# CW340_SAM3X_PWR.net
KiCad netlist of a schematic drawn in Altium Designer
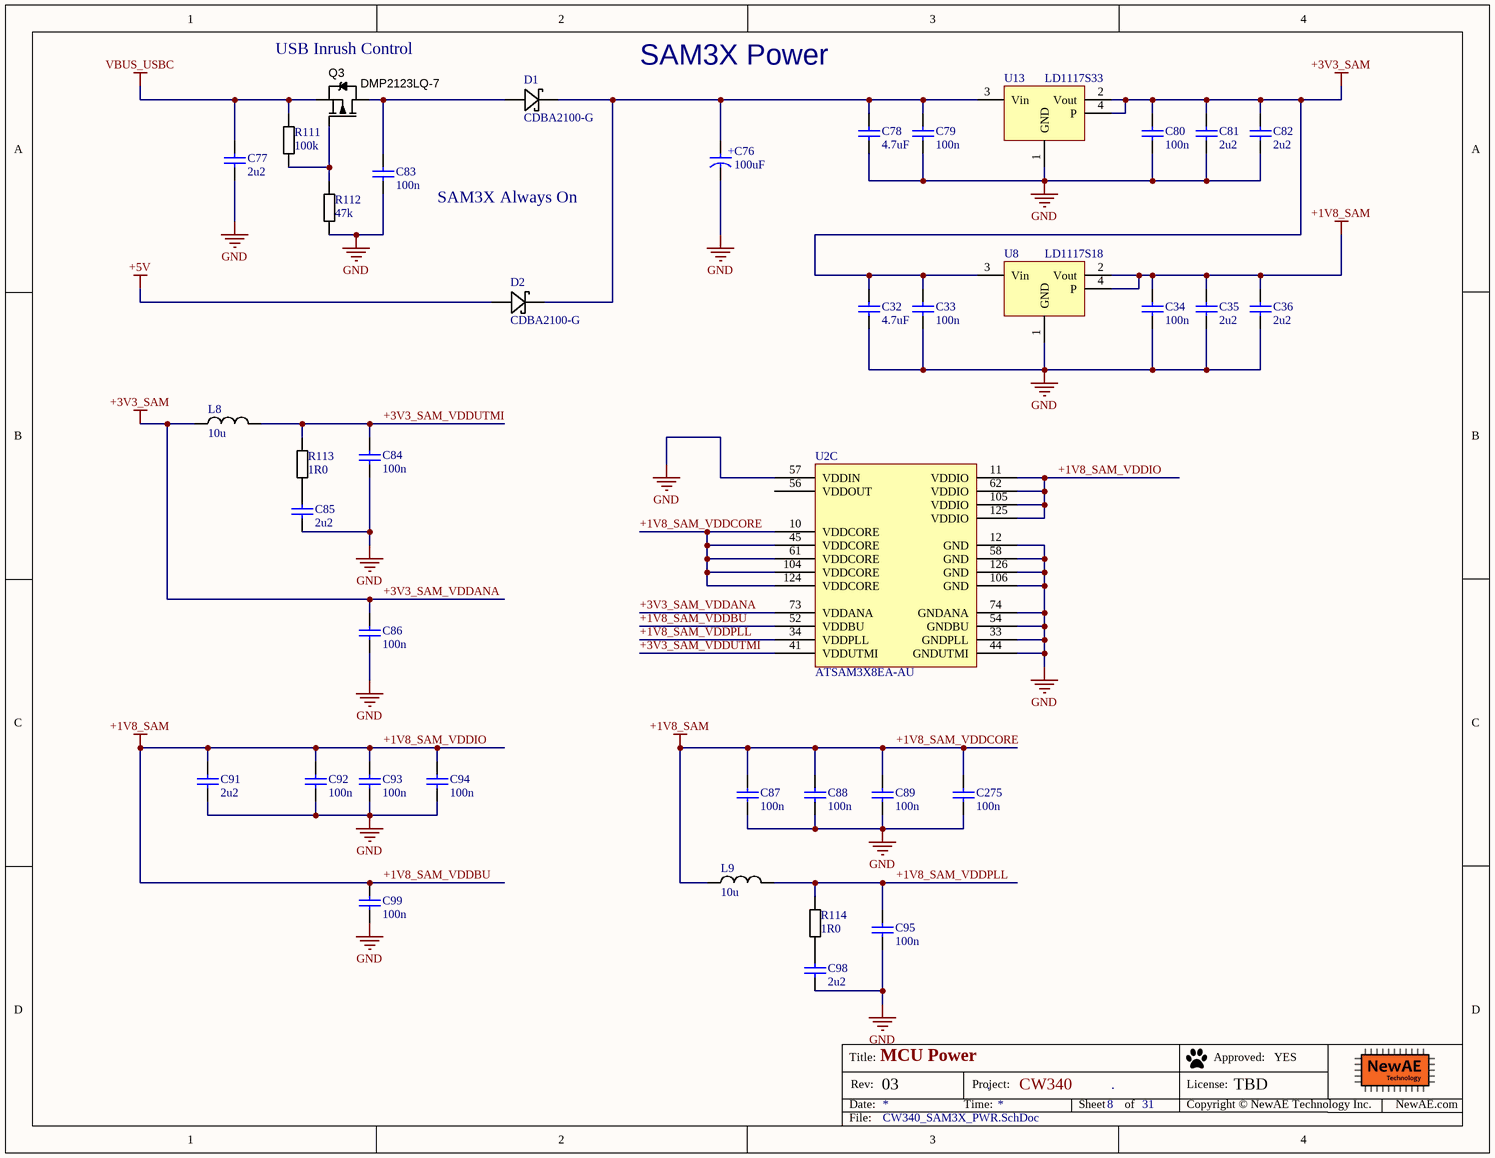
[diagram p0: CW340_SAM3X_PWR.SchDoc]

(export (version "E")
  (design (tool "Eeschema 10.0.6"))
  (components
    (comp (ref "C32")
      (value "4.7uF")
      (footprint "CAPC0805_M")
      (description "4u7, 35V, 0805, Ceramic")
      (fields (field (name "PART NUMBER") "CCHIP-4u7-0805-35V") (field (name "TOLERANCE") "10%"))
      (libsource (lib "NewAE_AltiumLib") (part "CAP"))
    )
    (comp (ref "C33")
      (value "100n")
      (footprint "CAPC0402_M")
      (description "100n, 0402")
      (fields (field (name "PART NUMBER") "CCHIP-100n-0402"))
      (libsource (lib "NewAE_AltiumLib") (part "CAP"))
    )
    (comp (ref "C34")
      (value "100n")
      (footprint "CAPC0402_M")
      (description "100n, 0402")
      (fields (field (name "PART NUMBER") "CCHIP-100n-0402"))
      (libsource (lib "NewAE_AltiumLib") (part "CAP"))
    )
    (comp (ref "C35")
      (value "2u2")
      (footprint "CAPC0603_M")
      (description "2u2, 0603")
      (fields (field (name "PART NUMBER") "CCHIP-2u2-0603"))
      (libsource (lib "NewAE_AltiumLib") (part "CAP"))
    )
    (comp (ref "C36")
      (value "2u2")
      (footprint "CAPC0603_M")
      (description "2u2, 0603")
      (fields (field (name "PART NUMBER") "CCHIP-2u2-0603"))
      (libsource (lib "NewAE_AltiumLib") (part "CAP"))
    )
    (comp (ref "C76")
      (value "100uF")
      (footprint "CAP_AL_D6.3")
      (description "CAP ALUM 100UF 20% 35V RADIAL")
      (fields (field (name "PART NUMBER") "Cap_35v_100uF"))
      (libsource (lib "NewAE_AltiumLib") (part "CAP_POL"))
    )
    (comp (ref "C77")
      (value "2u2")
      (footprint "CAPC0603_M")
      (description "2u2, 0603")
      (fields (field (name "PART NUMBER") "CCHIP-2u2-0603"))
      (libsource (lib "NewAE_AltiumLib") (part "CAP"))
    )
    (comp (ref "C78")
      (value "4.7uF")
      (footprint "CAPC0805_M")
      (description "4u7, 35V, 0805, Ceramic")
      (fields (field (name "PART NUMBER") "CCHIP-4u7-0805-35V") (field (name "TOLERANCE") "10%"))
      (libsource (lib "NewAE_AltiumLib") (part "CAP"))
    )
    (comp (ref "C79")
      (value "100n")
      (footprint "CAPC0402_M")
      (description "100n, 0402")
      (fields (field (name "PART NUMBER") "CCHIP-100n-0402"))
      (libsource (lib "NewAE_AltiumLib") (part "CAP"))
    )
    (comp (ref "C80")
      (value "100n")
      (footprint "CAPC0402_M")
      (description "100n, 0402")
      (fields (field (name "PART NUMBER") "CCHIP-100n-0402"))
      (libsource (lib "NewAE_AltiumLib") (part "CAP"))
    )
    (comp (ref "C81")
      (value "2u2")
      (footprint "CAPC0603_M")
      (description "2u2, 0603")
      (fields (field (name "PART NUMBER") "CCHIP-2u2-0603"))
      (libsource (lib "NewAE_AltiumLib") (part "CAP"))
    )
    (comp (ref "C82")
      (value "2u2")
      (footprint "CAPC0603_M")
      (description "2u2, 0603")
      (fields (field (name "PART NUMBER") "CCHIP-2u2-0603"))
      (libsource (lib "NewAE_AltiumLib") (part "CAP"))
    )
    (comp (ref "C83")
      (value "100n")
      (footprint "CAPC0402_M")
      (description "100n, 0402")
      (fields (field (name "PART NUMBER") "CCHIP-100n-0402"))
      (libsource (lib "NewAE_AltiumLib") (part "CAP"))
    )
    (comp (ref "C84")
      (value "100n")
      (footprint "CAPC0402_M")
      (description "100n, 0402")
      (fields (field (name "PART NUMBER") "CCHIP-100n-0402"))
      (libsource (lib "NewAE_AltiumLib") (part "CAP"))
    )
    (comp (ref "C85")
      (value "2u2")
      (footprint "CAPC0603_M")
      (description "2u2, 0603")
      (fields (field (name "PART NUMBER") "CCHIP-2u2-0603"))
      (libsource (lib "NewAE_AltiumLib") (part "CAP"))
    )
    (comp (ref "C86")
      (value "100n")
      (footprint "CAPC0402_M")
      (description "100n, 0402")
      (fields (field (name "PART NUMBER") "CCHIP-100n-0402"))
      (libsource (lib "NewAE_AltiumLib") (part "CAP"))
    )
    (comp (ref "C87")
      (value "100n")
      (footprint "CAPC0402_M")
      (description "100n, 0402")
      (fields (field (name "PART NUMBER") "CCHIP-100n-0402"))
      (libsource (lib "NewAE_AltiumLib") (part "CAP"))
    )
    (comp (ref "C88")
      (value "100n")
      (footprint "CAPC0402_M")
      (description "100n, 0402")
      (fields (field (name "PART NUMBER") "CCHIP-100n-0402"))
      (libsource (lib "NewAE_AltiumLib") (part "CAP"))
    )
    (comp (ref "C89")
      (value "100n")
      (footprint "CAPC0402_M")
      (description "100n, 0402")
      (fields (field (name "PART NUMBER") "CCHIP-100n-0402"))
      (libsource (lib "NewAE_AltiumLib") (part "CAP"))
    )
    (comp (ref "C91")
      (value "2u2")
      (footprint "CAPC0603_M")
      (description "2u2, 0603")
      (fields (field (name "PART NUMBER") "CCHIP-2u2-0603"))
      (libsource (lib "NewAE_AltiumLib") (part "CAP"))
    )
    (comp (ref "C92")
      (value "100n")
      (footprint "CAPC0402_M")
      (description "100n, 0402")
      (fields (field (name "PART NUMBER") "CCHIP-100n-0402"))
      (libsource (lib "NewAE_AltiumLib") (part "CAP"))
    )
    (comp (ref "C93")
      (value "100n")
      (footprint "CAPC0402_M")
      (description "100n, 0402")
      (fields (field (name "PART NUMBER") "CCHIP-100n-0402"))
      (libsource (lib "NewAE_AltiumLib") (part "CAP"))
    )
    (comp (ref "C94")
      (value "100n")
      (footprint "CAPC0402_M")
      (description "100n, 0402")
      (fields (field (name "PART NUMBER") "CCHIP-100n-0402"))
      (libsource (lib "NewAE_AltiumLib") (part "CAP"))
    )
    (comp (ref "C95")
      (value "100n")
      (footprint "CAPC0402_M")
      (description "100n, 0402")
      (fields (field (name "PART NUMBER") "CCHIP-100n-0402"))
      (libsource (lib "NewAE_AltiumLib") (part "CAP"))
    )
    (comp (ref "C98")
      (value "2u2")
      (footprint "CAPC0603_M")
      (description "2u2, 0603")
      (fields (field (name "PART NUMBER") "CCHIP-2u2-0603"))
      (libsource (lib "NewAE_AltiumLib") (part "CAP"))
    )
    (comp (ref "C99")
      (value "100n")
      (footprint "CAPC0402_M")
      (description "100n, 0402")
      (fields (field (name "PART NUMBER") "CCHIP-100n-0402"))
      (libsource (lib "NewAE_AltiumLib") (part "CAP"))
    )
    (comp (ref "C275")
      (value "100n")
      (footprint "CAPC0402_M")
      (description "100n, 0402")
      (fields (field (name "PART NUMBER") "CCHIP-100n-0402"))
      (libsource (lib "NewAE_AltiumLib") (part "CAP"))
    )
    (comp (ref "D1")
      (value "CDBA2100-G")
      (footprint "DO-214AC")
      (description "Diode Schottky, 100V, 2A")
      (libsource (lib "NewAE_AltiumLib") (part "DIODE_SCHOTTKY"))
    )
    (comp (ref "D2")
      (value "CDBA2100-G")
      (footprint "DO-214AC")
      (description "Diode Schottky, 100V, 2A")
      (libsource (lib "NewAE_AltiumLib") (part "DIODE_SCHOTTKY"))
    )
    (comp (ref "L8")
      (value "10u")
      (footprint "IND_0603")
      (description "FIXED IND 10UH 50MA 900 MOHM SMD")
      (fields (field (name "PART NUMBER") "LCHIP-10U-0603") (field (name "TOLERANCE") "±20%"))
      (libsource (lib "NewAE_AltiumLib") (part "IND"))
    )
    (comp (ref "L9")
      (value "10u")
      (footprint "IND_0603")
      (description "FIXED IND 10UH 50MA 900 MOHM SMD")
      (fields (field (name "PART NUMBER") "LCHIP-10U-0603") (field (name "TOLERANCE") "±20%"))
      (libsource (lib "NewAE_AltiumLib") (part "IND"))
    )
    (comp (ref "Q3")
      (value "DMP2123LQ-7")
      (footprint "SOT95P245X110-3M")
      (description "P-Channel, 3A, Logic Level")
      (libsource (lib "NewAE_AltiumLib") (part "MOSFET_P_GSD"))
    )
    (comp (ref "R111")
      (value "100k")
      (footprint "RESC1608X55N")
      (description "100k res, 0603, 1%, 1/10W")
      (fields (field (name "PART NUMBER") "RCHIP-100K-0603") (field (name "TOLERANCE") "1%"))
      (libsource (lib "NewAE_AltiumLib") (part "RES-EU"))
    )
    (comp (ref "R112")
      (value "47k")
      (footprint "RESC1608X55N")
      (description "47k res, 0603, 1%, 1/10W")
      (fields (field (name "PART NUMBER") "RCHIP-47K-0603") (field (name "TOLERANCE") "1%"))
      (libsource (lib "NewAE_AltiumLib") (part "RES-EU"))
    )
    (comp (ref "R113")
      (value "1R0")
      (footprint "RESC1608X55N")
      (description "1R0 res, 0603, 1%, 1/10W")
      (fields (field (name "PART NUMBER") "RCHIP-1R0-0603") (field (name "TOLERANCE") "1%"))
      (libsource (lib "NewAE_AltiumLib") (part "RES-EU"))
    )
    (comp (ref "R114")
      (value "1R0")
      (footprint "RESC1608X55N")
      (description "1R0 res, 0603, 1%, 1/10W")
      (fields (field (name "PART NUMBER") "RCHIP-1R0-0603") (field (name "TOLERANCE") "1%"))
      (libsource (lib "NewAE_AltiumLib") (part "RES-EU"))
    )
    (comp (ref "U2")
      (value "ATSAM3X8EA-AU")
      (footprint "LQFP144_L")
      (fields (field (name "MANUFACTURER") "Atmel"))
      (libsource (lib "Altium Content Vault") (part "ATML-ATSAM3X-LQFP-144"))
    )
    (comp (ref "U8")
      (value "LD1117S18")
      (footprint "SOT-223")
      (description "IC REG LIN POS 1.8V 800MA SOT223")
      (libsource (lib "NewAE_AltiumLib") (part "LD1117S33"))
    )
    (comp (ref "U13")
      (value "LD1117S33")
      (footprint "SOT-223")
      (description "IC REG LIN POS 3.3V 800MA SOT223")
      (libsource (lib "NewAE_AltiumLib") (part "LD1117S33"))
    )
  )
  (nets
    (net (code "1") (name "+1V8_SAM") (class "Default")
      (node (ref "C275") (pin "1") (pinfunction "1_1") (pintype "passive"))
      (node (ref "C34") (pin "1") (pinfunction "1_1") (pintype "passive"))
      (node (ref "C35") (pin "1") (pinfunction "1_1") (pintype "passive"))
      (node (ref "C36") (pin "1") (pinfunction "1_1") (pintype "passive"))
      (node (ref "C87") (pin "1") (pinfunction "1_1") (pintype "passive"))
      (node (ref "C88") (pin "1") (pinfunction "1_1") (pintype "passive"))
      (node (ref "C89") (pin "1") (pinfunction "1_1") (pintype "passive"))
      (node (ref "C91") (pin "1") (pinfunction "1_1") (pintype "passive"))
      (node (ref "C92") (pin "1") (pinfunction "1_1") (pintype "passive"))
      (node (ref "C93") (pin "1") (pinfunction "1_1") (pintype "passive"))
      (node (ref "C94") (pin "1") (pinfunction "1_1") (pintype "passive"))
      (node (ref "C99") (pin "1") (pinfunction "1_1") (pintype "passive"))
      (node (ref "L9") (pin "1") (pinfunction "1_1") (pintype "passive"))
      (node (ref "U2") (pin "10") (pinfunction "VDDCORE_10") (pintype "power_in"))
      (node (ref "U2") (pin "104") (pinfunction "VDDCORE_104") (pintype "power_in"))
      (node (ref "U2") (pin "105") (pinfunction "VDDIO_105") (pintype "power_in"))
      (node (ref "U2") (pin "11") (pinfunction "VDDIO_11") (pintype "power_in"))
      (node (ref "U2") (pin "124") (pinfunction "VDDCORE_124") (pintype "power_in"))
      (node (ref "U2") (pin "125") (pinfunction "VDDIO_125") (pintype "power_in"))
      (node (ref "U2") (pin "45") (pinfunction "VDDCORE_45") (pintype "power_in"))
      (node (ref "U2") (pin "52") (pinfunction "VDDBU_52") (pintype "power_in"))
      (node (ref "U2") (pin "61") (pinfunction "VDDCORE_61") (pintype "power_in"))
      (node (ref "U2") (pin "62") (pinfunction "VDDIO_62") (pintype "power_in"))
      (node (ref "U8") (pin "2") (pinfunction "Vout_2") (pintype "passive"))
      (node (ref "U8") (pin "4") (pinfunction "P_4") (pintype "passive"))
    )
    (net (code "2") (name "+3V3_SAM") (class "Default")
      (node (ref "C32") (pin "1") (pinfunction "1_1") (pintype "passive"))
      (node (ref "C33") (pin "1") (pinfunction "1_1") (pintype "passive"))
      (node (ref "C80") (pin "1") (pinfunction "1_1") (pintype "passive"))
      (node (ref "C81") (pin "1") (pinfunction "1_1") (pintype "passive"))
      (node (ref "C82") (pin "1") (pinfunction "1_1") (pintype "passive"))
      (node (ref "C86") (pin "1") (pinfunction "1_1") (pintype "passive"))
      (node (ref "L8") (pin "1") (pinfunction "1_1") (pintype "passive"))
      (node (ref "U13") (pin "2") (pinfunction "Vout_2") (pintype "passive"))
      (node (ref "U13") (pin "4") (pinfunction "P_4") (pintype "passive"))
      (node (ref "U2") (pin "73") (pinfunction "VDDANA_73") (pintype "power_in"))
      (node (ref "U8") (pin "3") (pinfunction "Vin_3") (pintype "passive"))
    )
    (net (code "3") (name "+5V") (class "Default")
      (node (ref "D2") (pin "A") (pinfunction "A_A") (pintype "passive"))
    )
    (net (code "4") (name "/+1V8_SAM_VDDPLL") (class "Default")
      (node (ref "C95") (pin "1") (pinfunction "1_1") (pintype "passive"))
      (node (ref "L9") (pin "2") (pinfunction "2_2") (pintype "passive"))
      (node (ref "R114") (pin "1") (pinfunction "1_1") (pintype "passive"))
      (node (ref "U2") (pin "34") (pinfunction "VDDPLL_34") (pintype "power_in"))
    )
    (net (code "5") (name "/+3V3_SAM_VDDUTMI") (class "Default")
      (node (ref "C84") (pin "1") (pinfunction "1_1") (pintype "passive"))
      (node (ref "L8") (pin "2") (pinfunction "2_2") (pintype "passive"))
      (node (ref "R113") (pin "1") (pinfunction "1_1") (pintype "passive"))
      (node (ref "U2") (pin "41") (pinfunction "VDDUTMI_41") (pintype "power_in"))
    )
    (net (code "6") (name "GND") (class "Default")
      (node (ref "C275") (pin "2") (pinfunction "2_2") (pintype "passive"))
      (node (ref "C32") (pin "2") (pinfunction "2_2") (pintype "passive"))
      (node (ref "C33") (pin "2") (pinfunction "2_2") (pintype "passive"))
      (node (ref "C34") (pin "2") (pinfunction "2_2") (pintype "passive"))
      (node (ref "C35") (pin "2") (pinfunction "2_2") (pintype "passive"))
      (node (ref "C36") (pin "2") (pinfunction "2_2") (pintype "passive"))
      (node (ref "C76") (pin "2") (pinfunction "2_2") (pintype "passive"))
      (node (ref "C77") (pin "2") (pinfunction "2_2") (pintype "passive"))
      (node (ref "C78") (pin "2") (pinfunction "2_2") (pintype "passive"))
      (node (ref "C79") (pin "2") (pinfunction "2_2") (pintype "passive"))
      (node (ref "C80") (pin "2") (pinfunction "2_2") (pintype "passive"))
      (node (ref "C81") (pin "2") (pinfunction "2_2") (pintype "passive"))
      (node (ref "C82") (pin "2") (pinfunction "2_2") (pintype "passive"))
      (node (ref "C83") (pin "2") (pinfunction "2_2") (pintype "passive"))
      (node (ref "C84") (pin "2") (pinfunction "2_2") (pintype "passive"))
      (node (ref "C85") (pin "2") (pinfunction "2_2") (pintype "passive"))
      (node (ref "C86") (pin "2") (pinfunction "2_2") (pintype "passive"))
      (node (ref "C87") (pin "2") (pinfunction "2_2") (pintype "passive"))
      (node (ref "C88") (pin "2") (pinfunction "2_2") (pintype "passive"))
      (node (ref "C89") (pin "2") (pinfunction "2_2") (pintype "passive"))
      (node (ref "C91") (pin "2") (pinfunction "2_2") (pintype "passive"))
      (node (ref "C92") (pin "2") (pinfunction "2_2") (pintype "passive"))
      (node (ref "C93") (pin "2") (pinfunction "2_2") (pintype "passive"))
      (node (ref "C94") (pin "2") (pinfunction "2_2") (pintype "passive"))
      (node (ref "C95") (pin "2") (pinfunction "2_2") (pintype "passive"))
      (node (ref "C98") (pin "2") (pinfunction "2_2") (pintype "passive"))
      (node (ref "C99") (pin "2") (pinfunction "2_2") (pintype "passive"))
      (node (ref "R112") (pin "2") (pinfunction "2_2") (pintype "passive"))
      (node (ref "U13") (pin "1") (pinfunction "GND_1") (pintype "passive"))
      (node (ref "U2") (pin "106") (pinfunction "GND_106") (pintype "power_in"))
      (node (ref "U2") (pin "12") (pinfunction "GND_12") (pintype "power_in"))
      (node (ref "U2") (pin "126") (pinfunction "GND_126") (pintype "power_in"))
      (node (ref "U2") (pin "33") (pinfunction "GNDPLL_33") (pintype "power_in"))
      (node (ref "U2") (pin "44") (pinfunction "GNDUTMI_44") (pintype "power_in"))
      (node (ref "U2") (pin "54") (pinfunction "GNDBU_54") (pintype "power_in"))
      (node (ref "U2") (pin "57") (pinfunction "VDDIN_57") (pintype "power_in"))
      (node (ref "U2") (pin "58") (pinfunction "GND_58") (pintype "power_in"))
      (node (ref "U2") (pin "74") (pinfunction "GNDANA_74") (pintype "power_in"))
      (node (ref "U8") (pin "1") (pinfunction "GND_1") (pintype "passive"))
    )
    (net (code "7") (name "Net-(C85-Pad1)") (class "Default")
      (node (ref "C85") (pin "1") (pinfunction "1_1") (pintype "passive"))
      (node (ref "R113") (pin "2") (pinfunction "2_2") (pintype "passive"))
    )
    (net (code "8") (name "Net-(C98-Pad1)") (class "Default")
      (node (ref "C98") (pin "1") (pinfunction "1_1") (pintype "passive"))
      (node (ref "R114") (pin "2") (pinfunction "2_2") (pintype "passive"))
    )
    (net (code "9") (name "Net-(Q3-D)") (class "Default")
      (node (ref "C83") (pin "1") (pinfunction "1_1") (pintype "passive"))
      (node (ref "D1") (pin "A") (pinfunction "A_A") (pintype "passive"))
      (node (ref "Q3") (pin "3") (pinfunction "D_3") (pintype "passive"))
    )
    (net (code "10") (name "Net-(Q3-G)") (class "Default")
      (node (ref "Q3") (pin "1") (pinfunction "G_1") (pintype "passive"))
      (node (ref "R111") (pin "2") (pinfunction "2_2") (pintype "passive"))
      (node (ref "R112") (pin "1") (pinfunction "1_1") (pintype "passive"))
    )
    (net (code "11") (name "Net-(U13-Vin)") (class "Default")
      (node (ref "C76") (pin "1") (pinfunction "1_1") (pintype "passive"))
      (node (ref "C78") (pin "1") (pinfunction "1_1") (pintype "passive"))
      (node (ref "C79") (pin "1") (pinfunction "1_1") (pintype "passive"))
      (node (ref "D1") (pin "K") (pinfunction "K_K") (pintype "passive"))
      (node (ref "D2") (pin "K") (pinfunction "K_K") (pintype "passive"))
      (node (ref "U13") (pin "3") (pinfunction "Vin_3") (pintype "passive"))
    )
    (net (code "12") (name "VBUS_USBC") (class "Default")
      (node (ref "C77") (pin "1") (pinfunction "1_1") (pintype "passive"))
      (node (ref "Q3") (pin "2") (pinfunction "S_2") (pintype "passive"))
      (node (ref "R111") (pin "1") (pinfunction "1_1") (pintype "passive"))
    )
    (net (code "13") (name "unconnected-(U2C-VDDOUT-Pad56)") (class "Default")
      (node (ref "U2") (pin "56") (pinfunction "VDDOUT_56") (pintype "power_in"))
    )
  )
)
